# Shift_Register_2IO_Breakout.net
KiCad netlist of a schematic drawn in EAGLE
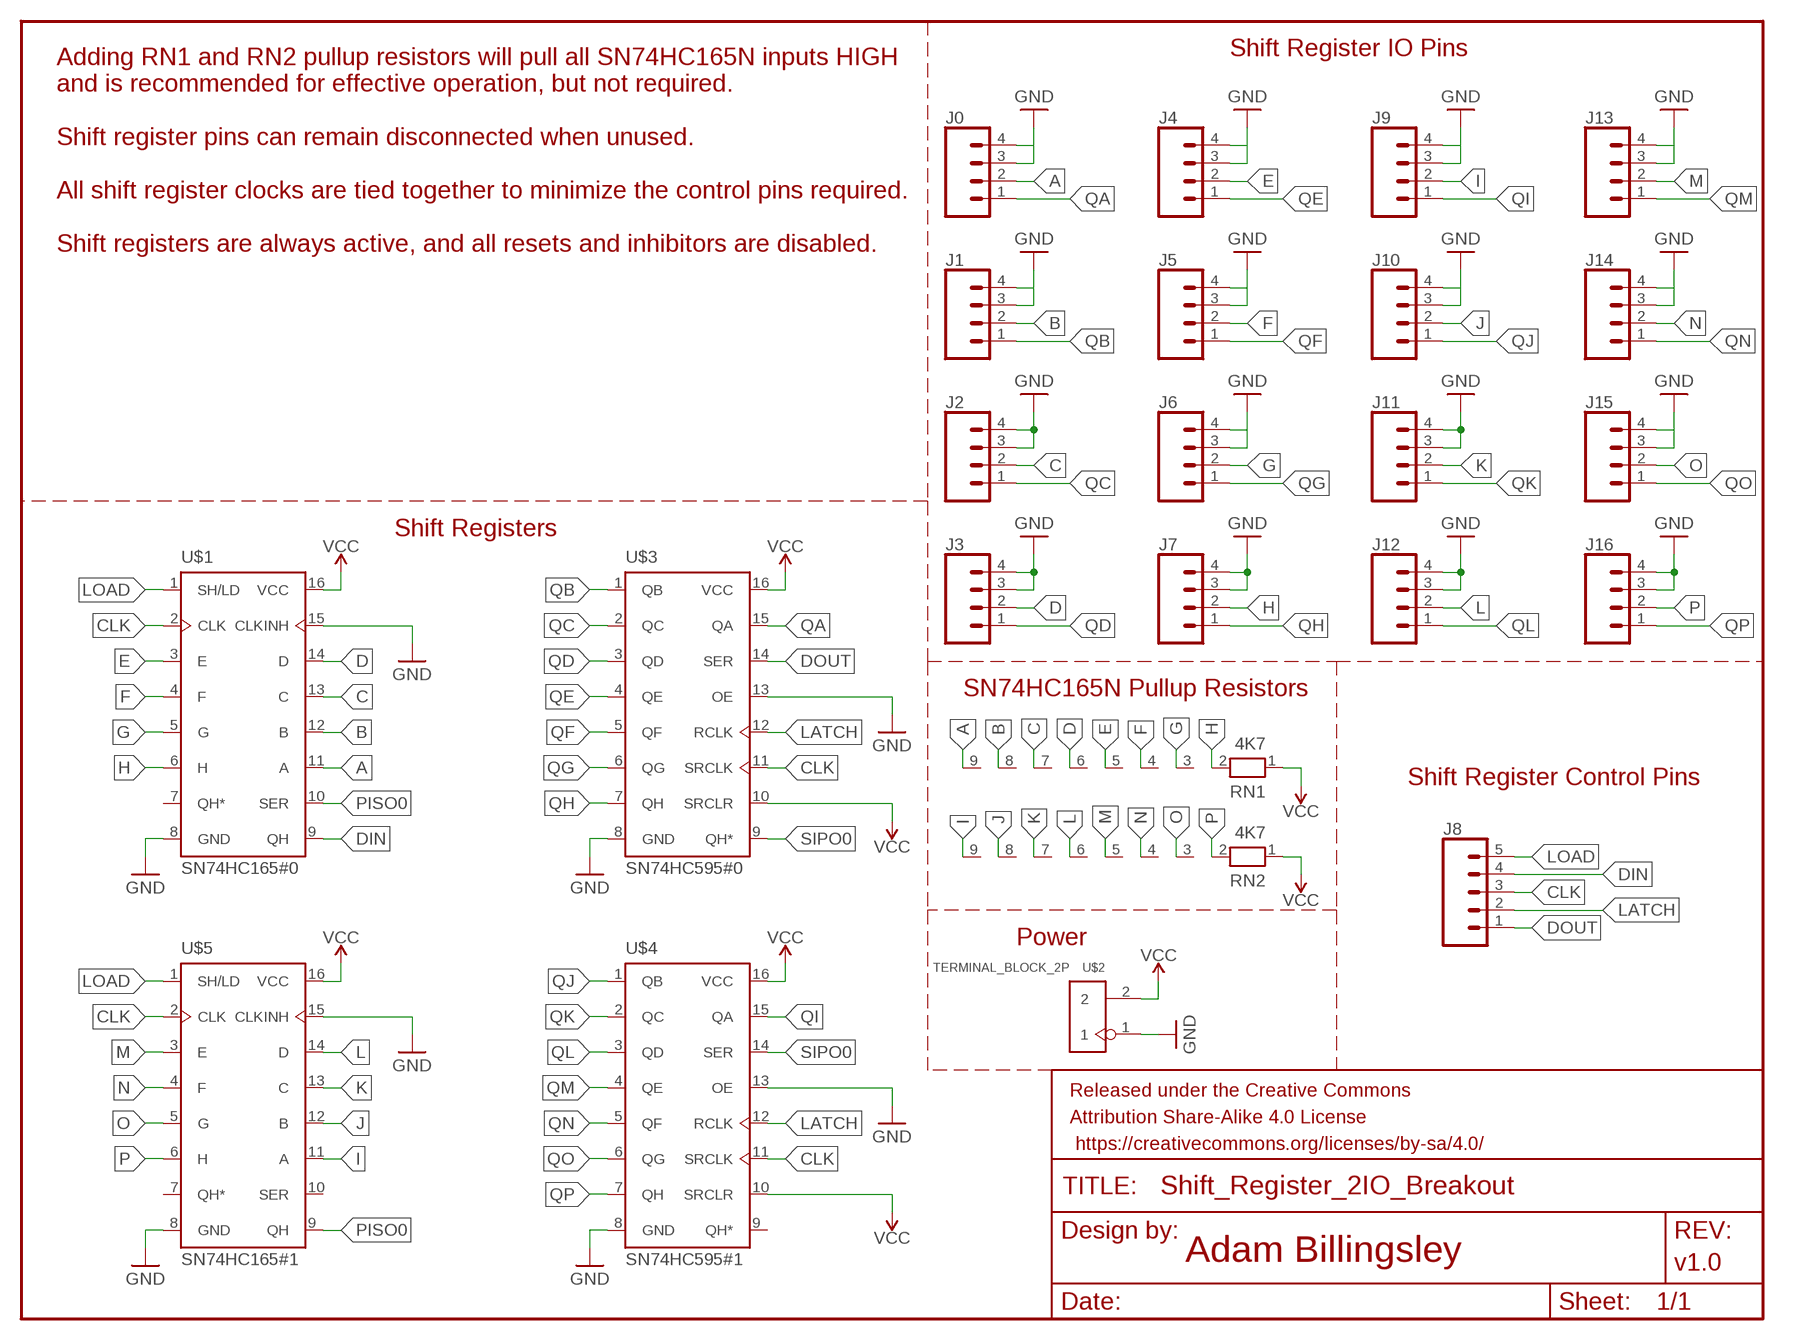
[diagram p0: schematic, sheet 1]

(export (version "E")
  (design (tool "Eeschema 10.0.6"))
  (components
    (comp (ref "FRAME1")
      (value "FRAME-LETTER")
      (footprint "eagle-import:CREATIVE_COMMONS")
      (libsource (lib "eagle-import") (part "FRAME-LETTER"))
    )
    (comp (ref "J0")
      (value "CONN_04")
      (footprint "eagle-import:1X04")
      (libsource (lib "eagle-import") (part "CONN_04"))
    )
    (comp (ref "J1")
      (value "CONN_04")
      (footprint "eagle-import:1X04")
      (libsource (lib "eagle-import") (part "CONN_04"))
    )
    (comp (ref "J2")
      (value "CONN_04")
      (footprint "eagle-import:1X04")
      (libsource (lib "eagle-import") (part "CONN_04"))
    )
    (comp (ref "J3")
      (value "CONN_04")
      (footprint "eagle-import:1X04")
      (libsource (lib "eagle-import") (part "CONN_04"))
    )
    (comp (ref "J4")
      (value "CONN_04")
      (footprint "eagle-import:1X04")
      (libsource (lib "eagle-import") (part "CONN_04"))
    )
    (comp (ref "J5")
      (value "CONN_04")
      (footprint "eagle-import:1X04")
      (libsource (lib "eagle-import") (part "CONN_04"))
    )
    (comp (ref "J6")
      (value "CONN_04")
      (footprint "eagle-import:1X04")
      (libsource (lib "eagle-import") (part "CONN_04"))
    )
    (comp (ref "J7")
      (value "CONN_04")
      (footprint "eagle-import:1X04")
      (libsource (lib "eagle-import") (part "CONN_04"))
    )
    (comp (ref "J8")
      (value "CONN_05")
      (footprint "eagle-import:1X05")
      (libsource (lib "eagle-import") (part "CONN_05"))
    )
    (comp (ref "J9")
      (value "CONN_04")
      (footprint "eagle-import:1X04")
      (libsource (lib "eagle-import") (part "CONN_04"))
    )
    (comp (ref "J10")
      (value "CONN_04")
      (footprint "eagle-import:1X04")
      (libsource (lib "eagle-import") (part "CONN_04"))
    )
    (comp (ref "J11")
      (value "CONN_04")
      (footprint "eagle-import:1X04")
      (libsource (lib "eagle-import") (part "CONN_04"))
    )
    (comp (ref "J12")
      (value "CONN_04")
      (footprint "eagle-import:1X04")
      (libsource (lib "eagle-import") (part "CONN_04"))
    )
    (comp (ref "J13")
      (value "CONN_04")
      (footprint "eagle-import:1X04")
      (libsource (lib "eagle-import") (part "CONN_04"))
    )
    (comp (ref "J14")
      (value "CONN_04")
      (footprint "eagle-import:1X04")
      (libsource (lib "eagle-import") (part "CONN_04"))
    )
    (comp (ref "J15")
      (value "CONN_04")
      (footprint "eagle-import:1X04")
      (libsource (lib "eagle-import") (part "CONN_04"))
    )
    (comp (ref "J16")
      (value "CONN_04")
      (footprint "eagle-import:1X04")
      (libsource (lib "eagle-import") (part "CONN_04"))
    )
    (comp (ref "RN1")
      (value "4K7")
      (footprint "eagle-import:RN-9")
      (libsource (lib "eagle-import") (part "RN08"))
    )
    (comp (ref "RN2")
      (value "4K7")
      (footprint "eagle-import:RN-9")
      (libsource (lib "eagle-import") (part "RN08"))
    )
    (comp (ref "U$1")
      (value "SN74HC165#0")
      (footprint "eagle-import:DIL16")
      (libsource (lib "eagle-import") (part "SN74HC165"))
    )
    (comp (ref "U$2")
      (value "TERMINAL_BLOCK_2P")
      (footprint "eagle-import:H2-5.0-10.5X8.0MM")
      (libsource (lib "eagle-import") (part "TERMINAL_BLOCK_2P"))
    )
    (comp (ref "U$3")
      (value "SN74HC595#0")
      (footprint "eagle-import:DIL16")
      (libsource (lib "eagle-import") (part "SN74HC595"))
    )
    (comp (ref "U$4")
      (value "SN74HC595#1")
      (footprint "eagle-import:DIL16")
      (libsource (lib "eagle-import") (part "SN74HC595"))
    )
    (comp (ref "U$5")
      (value "SN74HC165#1")
      (footprint "eagle-import:DIL16")
      (libsource (lib "eagle-import") (part "SN74HC165"))
    )
  )
  (nets
    (net (code "1") (name "A") (class "Default")
      (node (ref "J0") (pin "2") (pinfunction "2_2") (pintype "passive"))
      (node (ref "RN1") (pin "9") (pinfunction "9_9") (pintype "passive"))
      (node (ref "U$1") (pin "11") (pinfunction "A_11") (pintype "input"))
    )
    (net (code "2") (name "B") (class "Default")
      (node (ref "J1") (pin "2") (pinfunction "2_2") (pintype "passive"))
      (node (ref "RN1") (pin "8") (pinfunction "8_8") (pintype "passive"))
      (node (ref "U$1") (pin "12") (pinfunction "B_12") (pintype "input"))
    )
    (net (code "3") (name "C") (class "Default")
      (node (ref "J2") (pin "2") (pinfunction "2_2") (pintype "passive"))
      (node (ref "RN1") (pin "7") (pinfunction "7_7") (pintype "passive"))
      (node (ref "U$1") (pin "13") (pinfunction "C_13") (pintype "input"))
    )
    (net (code "4") (name "CLK") (class "Default")
      (node (ref "J8") (pin "3") (pinfunction "3_3") (pintype "passive"))
      (node (ref "U$1") (pin "2") (pinfunction "CLK_2") (pintype "input"))
      (node (ref "U$3") (pin "11") (pinfunction "SRCLK_11") (pintype "input"))
      (node (ref "U$4") (pin "11") (pinfunction "SRCLK_11") (pintype "input"))
      (node (ref "U$5") (pin "2") (pinfunction "CLK_2") (pintype "input"))
    )
    (net (code "5") (name "D") (class "Default")
      (node (ref "J3") (pin "2") (pinfunction "2_2") (pintype "passive"))
      (node (ref "RN1") (pin "6") (pinfunction "6_6") (pintype "passive"))
      (node (ref "U$1") (pin "14") (pinfunction "D_14") (pintype "input"))
    )
    (net (code "6") (name "DIN") (class "Default")
      (node (ref "J8") (pin "4") (pinfunction "4_4") (pintype "passive"))
      (node (ref "U$1") (pin "9") (pinfunction "QH_9") (pintype "output"))
    )
    (net (code "7") (name "DOUT") (class "Default")
      (node (ref "J8") (pin "1") (pinfunction "1_1") (pintype "passive"))
      (node (ref "U$3") (pin "14") (pinfunction "SER_14") (pintype "input"))
    )
    (net (code "8") (name "E") (class "Default")
      (node (ref "J4") (pin "2") (pinfunction "2_2") (pintype "passive"))
      (node (ref "RN1") (pin "5") (pinfunction "5_5") (pintype "passive"))
      (node (ref "U$1") (pin "3") (pinfunction "E_3") (pintype "input"))
    )
    (net (code "9") (name "F") (class "Default")
      (node (ref "J5") (pin "2") (pinfunction "2_2") (pintype "passive"))
      (node (ref "RN1") (pin "4") (pinfunction "4_4") (pintype "passive"))
      (node (ref "U$1") (pin "4") (pinfunction "F_4") (pintype "input"))
    )
    (net (code "10") (name "G") (class "Default")
      (node (ref "J6") (pin "2") (pinfunction "2_2") (pintype "passive"))
      (node (ref "RN1") (pin "3") (pinfunction "3_3") (pintype "passive"))
      (node (ref "U$1") (pin "5") (pinfunction "G_5") (pintype "input"))
    )
    (net (code "11") (name "GND") (class "Default")
      (node (ref "J0") (pin "3") (pinfunction "3_3") (pintype "passive"))
      (node (ref "J0") (pin "4") (pinfunction "4_4") (pintype "passive"))
      (node (ref "J1") (pin "3") (pinfunction "3_3") (pintype "passive"))
      (node (ref "J1") (pin "4") (pinfunction "4_4") (pintype "passive"))
      (node (ref "J10") (pin "3") (pinfunction "3_3") (pintype "passive"))
      (node (ref "J10") (pin "4") (pinfunction "4_4") (pintype "passive"))
      (node (ref "J11") (pin "3") (pinfunction "3_3") (pintype "passive"))
      (node (ref "J11") (pin "4") (pinfunction "4_4") (pintype "passive"))
      (node (ref "J12") (pin "3") (pinfunction "3_3") (pintype "passive"))
      (node (ref "J12") (pin "4") (pinfunction "4_4") (pintype "passive"))
      (node (ref "J13") (pin "3") (pinfunction "3_3") (pintype "passive"))
      (node (ref "J13") (pin "4") (pinfunction "4_4") (pintype "passive"))
      (node (ref "J14") (pin "3") (pinfunction "3_3") (pintype "passive"))
      (node (ref "J14") (pin "4") (pinfunction "4_4") (pintype "passive"))
      (node (ref "J15") (pin "3") (pinfunction "3_3") (pintype "passive"))
      (node (ref "J15") (pin "4") (pinfunction "4_4") (pintype "passive"))
      (node (ref "J16") (pin "3") (pinfunction "3_3") (pintype "passive"))
      (node (ref "J16") (pin "4") (pinfunction "4_4") (pintype "passive"))
      (node (ref "J2") (pin "3") (pinfunction "3_3") (pintype "passive"))
      (node (ref "J2") (pin "4") (pinfunction "4_4") (pintype "passive"))
      (node (ref "J3") (pin "3") (pinfunction "3_3") (pintype "passive"))
      (node (ref "J3") (pin "4") (pinfunction "4_4") (pintype "passive"))
      (node (ref "J4") (pin "3") (pinfunction "3_3") (pintype "passive"))
      (node (ref "J4") (pin "4") (pinfunction "4_4") (pintype "passive"))
      (node (ref "J5") (pin "3") (pinfunction "3_3") (pintype "passive"))
      (node (ref "J5") (pin "4") (pinfunction "4_4") (pintype "passive"))
      (node (ref "J6") (pin "3") (pinfunction "3_3") (pintype "passive"))
      (node (ref "J6") (pin "4") (pinfunction "4_4") (pintype "passive"))
      (node (ref "J7") (pin "3") (pinfunction "3_3") (pintype "passive"))
      (node (ref "J7") (pin "4") (pinfunction "4_4") (pintype "passive"))
      (node (ref "J9") (pin "3") (pinfunction "3_3") (pintype "passive"))
      (node (ref "J9") (pin "4") (pinfunction "4_4") (pintype "passive"))
      (node (ref "U$1") (pin "15") (pinfunction "CLKINH_15") (pintype "input"))
      (node (ref "U$1") (pin "8") (pinfunction "GND_8") (pintype "power_in"))
      (node (ref "U$2") (pin "1") (pinfunction "1_1") (pintype "bidirectional"))
      (node (ref "U$3") (pin "13") (pinfunction "OE_13") (pintype "open_collector"))
      (node (ref "U$3") (pin "8") (pinfunction "GND_8") (pintype "power_in"))
      (node (ref "U$4") (pin "13") (pinfunction "OE_13") (pintype "open_collector"))
      (node (ref "U$4") (pin "8") (pinfunction "GND_8") (pintype "power_in"))
      (node (ref "U$5") (pin "15") (pinfunction "CLKINH_15") (pintype "input"))
      (node (ref "U$5") (pin "8") (pinfunction "GND_8") (pintype "power_in"))
    )
    (net (code "12") (name "H") (class "Default")
      (node (ref "J7") (pin "2") (pinfunction "2_2") (pintype "passive"))
      (node (ref "RN1") (pin "2") (pinfunction "2_2") (pintype "passive"))
      (node (ref "U$1") (pin "6") (pinfunction "H_6") (pintype "input"))
    )
    (net (code "13") (name "I") (class "Default")
      (node (ref "J9") (pin "2") (pinfunction "2_2") (pintype "passive"))
      (node (ref "RN2") (pin "9") (pinfunction "9_9") (pintype "passive"))
      (node (ref "U$5") (pin "11") (pinfunction "A_11") (pintype "input"))
    )
    (net (code "14") (name "J") (class "Default")
      (node (ref "J10") (pin "2") (pinfunction "2_2") (pintype "passive"))
      (node (ref "RN2") (pin "8") (pinfunction "8_8") (pintype "passive"))
      (node (ref "U$5") (pin "12") (pinfunction "B_12") (pintype "input"))
    )
    (net (code "15") (name "K") (class "Default")
      (node (ref "J11") (pin "2") (pinfunction "2_2") (pintype "passive"))
      (node (ref "RN2") (pin "7") (pinfunction "7_7") (pintype "passive"))
      (node (ref "U$5") (pin "13") (pinfunction "C_13") (pintype "input"))
    )
    (net (code "16") (name "L") (class "Default")
      (node (ref "J12") (pin "2") (pinfunction "2_2") (pintype "passive"))
      (node (ref "RN2") (pin "6") (pinfunction "6_6") (pintype "passive"))
      (node (ref "U$5") (pin "14") (pinfunction "D_14") (pintype "input"))
    )
    (net (code "17") (name "LATCH") (class "Default")
      (node (ref "J8") (pin "2") (pinfunction "2_2") (pintype "passive"))
      (node (ref "U$3") (pin "12") (pinfunction "RCLK_12") (pintype "input"))
      (node (ref "U$4") (pin "12") (pinfunction "RCLK_12") (pintype "input"))
    )
    (net (code "18") (name "LOAD") (class "Default")
      (node (ref "J8") (pin "5") (pinfunction "5_5") (pintype "passive"))
      (node (ref "U$1") (pin "1") (pinfunction "SH/LD_1") (pintype "open_collector"))
      (node (ref "U$5") (pin "1") (pinfunction "SH/LD_1") (pintype "open_collector"))
    )
    (net (code "19") (name "M") (class "Default")
      (node (ref "J13") (pin "2") (pinfunction "2_2") (pintype "passive"))
      (node (ref "RN2") (pin "5") (pinfunction "5_5") (pintype "passive"))
      (node (ref "U$5") (pin "3") (pinfunction "E_3") (pintype "input"))
    )
    (net (code "20") (name "N") (class "Default")
      (node (ref "J14") (pin "2") (pinfunction "2_2") (pintype "passive"))
      (node (ref "RN2") (pin "4") (pinfunction "4_4") (pintype "passive"))
      (node (ref "U$5") (pin "4") (pinfunction "F_4") (pintype "input"))
    )
    (net (code "21") (name "O") (class "Default")
      (node (ref "J15") (pin "2") (pinfunction "2_2") (pintype "passive"))
      (node (ref "RN2") (pin "3") (pinfunction "3_3") (pintype "passive"))
      (node (ref "U$5") (pin "5") (pinfunction "G_5") (pintype "input"))
    )
    (net (code "22") (name "P") (class "Default")
      (node (ref "J16") (pin "2") (pinfunction "2_2") (pintype "passive"))
      (node (ref "RN2") (pin "2") (pinfunction "2_2") (pintype "passive"))
      (node (ref "U$5") (pin "6") (pinfunction "H_6") (pintype "input"))
    )
    (net (code "23") (name "PISO0") (class "Default")
      (node (ref "U$1") (pin "10") (pinfunction "SER_10") (pintype "input"))
      (node (ref "U$5") (pin "9") (pinfunction "QH_9") (pintype "output"))
    )
    (net (code "24") (name "QA") (class "Default")
      (node (ref "J0") (pin "1") (pinfunction "1_1") (pintype "passive"))
      (node (ref "U$3") (pin "15") (pinfunction "QA_15") (pintype "output"))
    )
    (net (code "25") (name "QB") (class "Default")
      (node (ref "J1") (pin "1") (pinfunction "1_1") (pintype "passive"))
      (node (ref "U$3") (pin "1") (pinfunction "QB_1") (pintype "output"))
    )
    (net (code "26") (name "QC") (class "Default")
      (node (ref "J2") (pin "1") (pinfunction "1_1") (pintype "passive"))
      (node (ref "U$3") (pin "2") (pinfunction "QC_2") (pintype "output"))
    )
    (net (code "27") (name "QD") (class "Default")
      (node (ref "J3") (pin "1") (pinfunction "1_1") (pintype "passive"))
      (node (ref "U$3") (pin "3") (pinfunction "QD_3") (pintype "output"))
    )
    (net (code "28") (name "QE") (class "Default")
      (node (ref "J4") (pin "1") (pinfunction "1_1") (pintype "passive"))
      (node (ref "U$3") (pin "4") (pinfunction "QE_4") (pintype "output"))
    )
    (net (code "29") (name "QF") (class "Default")
      (node (ref "J5") (pin "1") (pinfunction "1_1") (pintype "passive"))
      (node (ref "U$3") (pin "5") (pinfunction "QF_5") (pintype "output"))
    )
    (net (code "30") (name "QG") (class "Default")
      (node (ref "J6") (pin "1") (pinfunction "1_1") (pintype "passive"))
      (node (ref "U$3") (pin "6") (pinfunction "QG_6") (pintype "output"))
    )
    (net (code "31") (name "QH") (class "Default")
      (node (ref "J7") (pin "1") (pinfunction "1_1") (pintype "passive"))
      (node (ref "U$3") (pin "7") (pinfunction "QH_7") (pintype "output"))
    )
    (net (code "32") (name "QI") (class "Default")
      (node (ref "J9") (pin "1") (pinfunction "1_1") (pintype "passive"))
      (node (ref "U$4") (pin "15") (pinfunction "QA_15") (pintype "output"))
    )
    (net (code "33") (name "QJ") (class "Default")
      (node (ref "J10") (pin "1") (pinfunction "1_1") (pintype "passive"))
      (node (ref "U$4") (pin "1") (pinfunction "QB_1") (pintype "output"))
    )
    (net (code "34") (name "QK") (class "Default")
      (node (ref "J11") (pin "1") (pinfunction "1_1") (pintype "passive"))
      (node (ref "U$4") (pin "2") (pinfunction "QC_2") (pintype "output"))
    )
    (net (code "35") (name "QL") (class "Default")
      (node (ref "J12") (pin "1") (pinfunction "1_1") (pintype "passive"))
      (node (ref "U$4") (pin "3") (pinfunction "QD_3") (pintype "output"))
    )
    (net (code "36") (name "QM") (class "Default")
      (node (ref "J13") (pin "1") (pinfunction "1_1") (pintype "passive"))
      (node (ref "U$4") (pin "4") (pinfunction "QE_4") (pintype "output"))
    )
    (net (code "37") (name "QN") (class "Default")
      (node (ref "J14") (pin "1") (pinfunction "1_1") (pintype "passive"))
      (node (ref "U$4") (pin "5") (pinfunction "QF_5") (pintype "output"))
    )
    (net (code "38") (name "QO") (class "Default")
      (node (ref "J15") (pin "1") (pinfunction "1_1") (pintype "passive"))
      (node (ref "U$4") (pin "6") (pinfunction "QG_6") (pintype "output"))
    )
    (net (code "39") (name "QP") (class "Default")
      (node (ref "J16") (pin "1") (pinfunction "1_1") (pintype "passive"))
      (node (ref "U$4") (pin "7") (pinfunction "QH_7") (pintype "output"))
    )
    (net (code "40") (name "SIPO0") (class "Default")
      (node (ref "U$3") (pin "9") (pinfunction "QH*_9") (pintype "output"))
      (node (ref "U$4") (pin "14") (pinfunction "SER_14") (pintype "input"))
    )
    (net (code "41") (name "VCC") (class "Default")
      (node (ref "RN1") (pin "1") (pinfunction "1_1") (pintype "passive"))
      (node (ref "RN2") (pin "1") (pinfunction "1_1") (pintype "passive"))
      (node (ref "U$1") (pin "16") (pinfunction "VCC_16") (pintype "power_in"))
      (node (ref "U$2") (pin "2") (pinfunction "2_2") (pintype "bidirectional"))
      (node (ref "U$3") (pin "10") (pinfunction "SRCLR_10") (pintype "open_collector"))
      (node (ref "U$3") (pin "16") (pinfunction "VCC_16") (pintype "power_in"))
      (node (ref "U$4") (pin "10") (pinfunction "SRCLR_10") (pintype "open_collector"))
      (node (ref "U$4") (pin "16") (pinfunction "VCC_16") (pintype "power_in"))
      (node (ref "U$5") (pin "16") (pinfunction "VCC_16") (pintype "power_in"))
    )
    (net (code "42") (name "unconnected-(U$1-QH*-Pad7)") (class "Default")
      (node (ref "U$1") (pin "7") (pinfunction "QH*_7") (pintype "output"))
    )
    (net (code "43") (name "unconnected-(U$4-QH*-Pad9)") (class "Default")
      (node (ref "U$4") (pin "9") (pinfunction "QH*_9") (pintype "output"))
    )
    (net (code "44") (name "unconnected-(U$5-QH*-Pad7)") (class "Default")
      (node (ref "U$5") (pin "7") (pinfunction "QH*_7") (pintype "output"))
    )
    (net (code "45") (name "unconnected-(U$5-SER-Pad10)") (class "Default")
      (node (ref "U$5") (pin "10") (pinfunction "SER_10") (pintype "input"))
    )
  )
)
